# EasyEDA-Schematic.net
KiCad netlist of a schematic drawn in EasyEDA
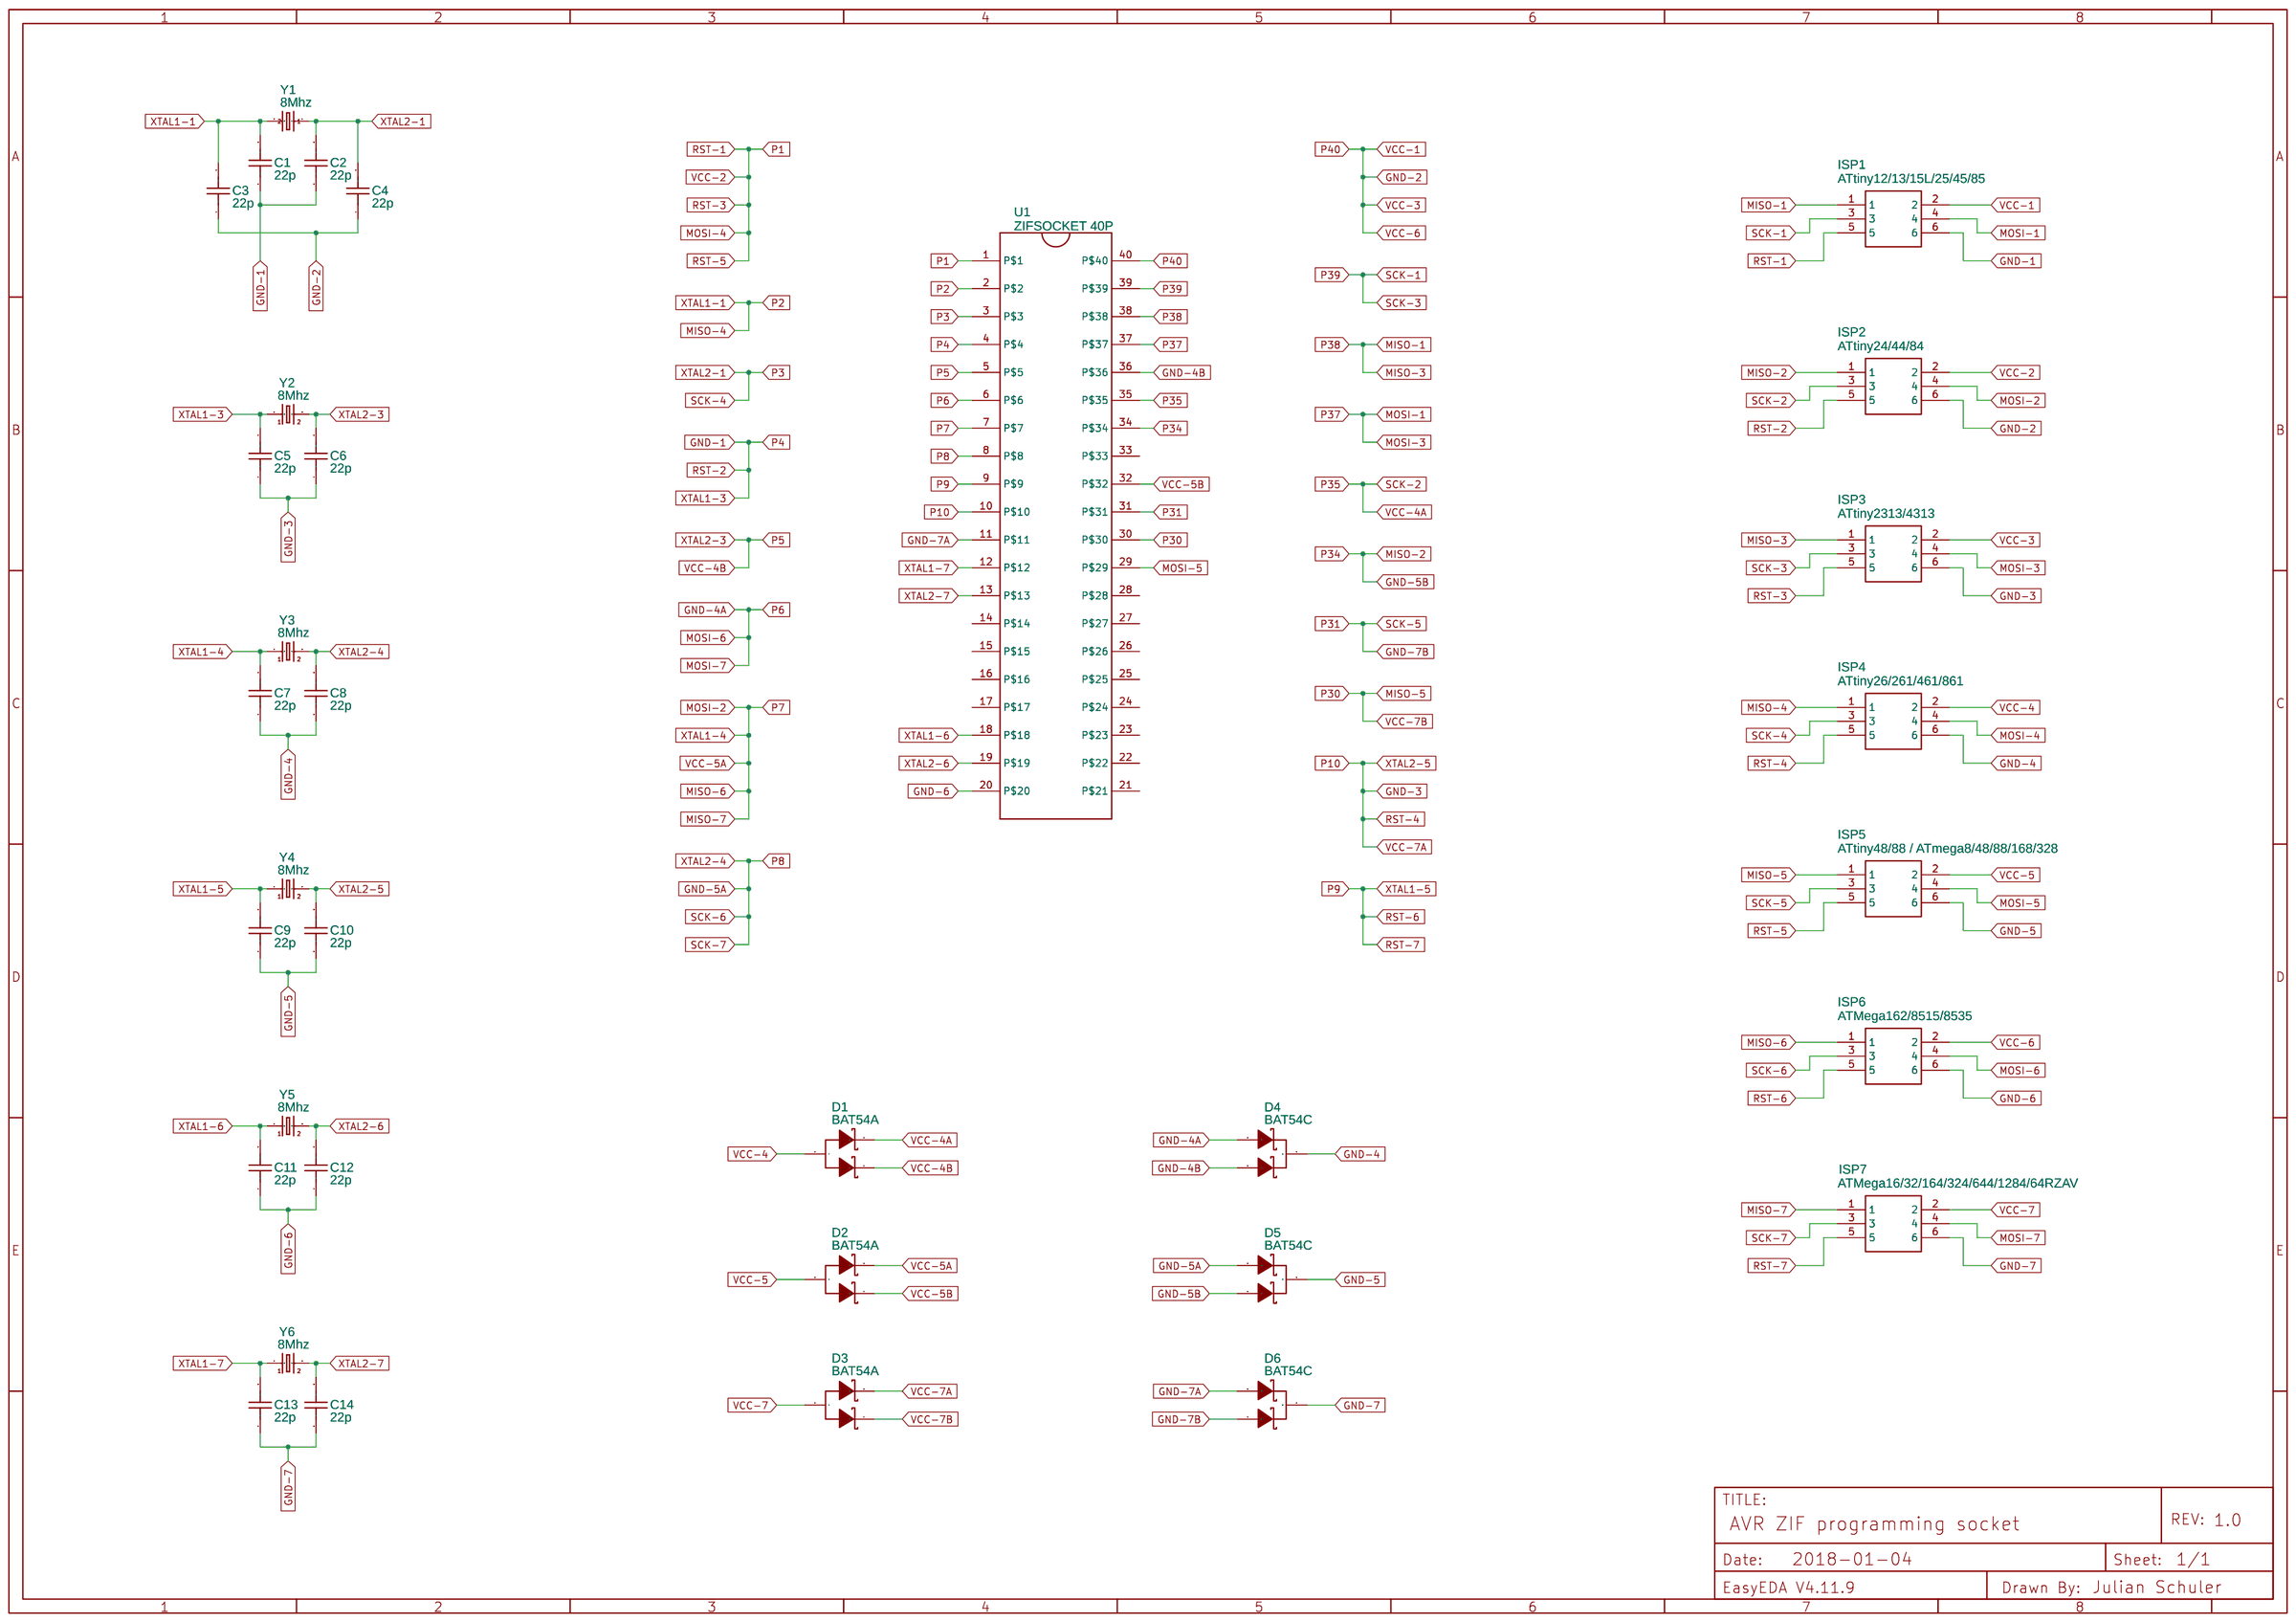
[diagram p0: schematic sheet]

(export (version "E")
  (design (tool "Eeschema 10.0.6"))
  (components
    (comp (ref "C1")
      (value "22p")
      (fields (field (name "BOM_Manufacturer Part") "?"))
      (libsource (lib "") (part "Cap_RAD-0.1_US"))
    )
    (comp (ref "C2")
      (value "22p")
      (fields (field (name "BOM_Manufacturer Part") "?"))
      (libsource (lib "") (part "Cap_RAD-0.1_US"))
    )
    (comp (ref "C3")
      (value "22p")
      (fields (field (name "BOM_Manufacturer Part") "?"))
      (libsource (lib "") (part "Cap_RAD-0.1_US"))
    )
    (comp (ref "C4")
      (value "22p")
      (fields (field (name "BOM_Manufacturer Part") "?"))
      (libsource (lib "") (part "Cap_RAD-0.1_US"))
    )
    (comp (ref "C5")
      (value "22p")
      (fields (field (name "BOM_Manufacturer Part") "?"))
      (libsource (lib "") (part "Cap_RAD-0.1_US"))
    )
    (comp (ref "C6")
      (value "22p")
      (fields (field (name "BOM_Manufacturer Part") "?"))
      (libsource (lib "") (part "Cap_RAD-0.1_US"))
    )
    (comp (ref "C7")
      (value "22p")
      (fields (field (name "BOM_Manufacturer Part") "?"))
      (libsource (lib "") (part "Cap_RAD-0.1_US"))
    )
    (comp (ref "C8")
      (value "22p")
      (fields (field (name "BOM_Manufacturer Part") "?"))
      (libsource (lib "") (part "Cap_RAD-0.1_US"))
    )
    (comp (ref "C9")
      (value "22p")
      (fields (field (name "BOM_Manufacturer Part") "?"))
      (libsource (lib "") (part "Cap_RAD-0.1_US"))
    )
    (comp (ref "C10")
      (value "22p")
      (fields (field (name "BOM_Manufacturer Part") "?"))
      (libsource (lib "") (part "Cap_RAD-0.1_US"))
    )
    (comp (ref "C11")
      (value "22p")
      (fields (field (name "BOM_Manufacturer Part") "?"))
      (libsource (lib "") (part "Cap_RAD-0.1_US"))
    )
    (comp (ref "C12")
      (value "22p")
      (fields (field (name "BOM_Manufacturer Part") "?"))
      (libsource (lib "") (part "Cap_RAD-0.1_US"))
    )
    (comp (ref "C13")
      (value "22p")
      (fields (field (name "BOM_Manufacturer Part") "?"))
      (libsource (lib "") (part "Cap_RAD-0.1_US"))
    )
    (comp (ref "C14")
      (value "22p")
      (fields (field (name "BOM_Manufacturer Part") "?"))
      (libsource (lib "") (part "Cap_RAD-0.1_US"))
    )
    (comp (ref "D1")
      (value "BAT54A")
      (fields (field (name "BOM_Supplier Part") "C83936"))
      (libsource (lib "") (part "Unknown_590_820"))
    )
    (comp (ref "D2")
      (value "BAT54A")
      (fields (field (name "BOM_Supplier Part") "C83936"))
      (libsource (lib "") (part "Unknown_590_910"))
    )
    (comp (ref "D3")
      (value "BAT54A")
      (fields (field (name "BOM_Supplier Part") "C83936"))
      (libsource (lib "") (part "Unknown_590_1000"))
    )
    (comp (ref "D4")
      (value "BAT54C")
      (fields
        (field (name "BOM_Manufacturer Part") "BAT54C(L43)")
        (field (name "BOM_Supplier Part") "C118748")
      )
      (libsource (lib "") (part "Unknown_900_820"))
    )
    (comp (ref "D5")
      (value "BAT54C")
      (fields
        (field (name "BOM_Manufacturer Part") "BAT54C(L43)")
        (field (name "BOM_Supplier Part") "C118748")
      )
      (libsource (lib "") (part "Unknown_900_910"))
    )
    (comp (ref "D6")
      (value "BAT54C")
      (fields
        (field (name "BOM_Manufacturer Part") "BAT54C(L43)")
        (field (name "BOM_Supplier Part") "C118748")
      )
      (libsource (lib "") (part "Unknown_900_1000"))
    )
    (comp (ref "ISP1")
      (value "ATtiny12/13/15L/25/45/85")
      (fields
        (field (name "BOM_Manufacturer Part") "2X3 2.54mm IDC Box")
        (field (name "BOM_Supplier Part") "C11214")
      )
      (libsource (lib "") (part "Unknown_1350_170"))
    )
    (comp (ref "ISP2")
      (value "ATtiny24/44/84")
      (fields
        (field (name "BOM_Manufacturer Part") "2X3 2.54mm IDC Box")
        (field (name "BOM_Supplier Part") "C11214")
      )
      (libsource (lib "") (part "Unknown_1350_290"))
    )
    (comp (ref "ISP3")
      (value "ATtiny2313/4313")
      (fields
        (field (name "BOM_Manufacturer Part") "2X3 2.54mm IDC Box")
        (field (name "BOM_Supplier Part") "C11214")
      )
      (libsource (lib "") (part "Unknown_1350_410"))
    )
    (comp (ref "ISP4")
      (value "ATtiny26/261/461/861")
      (fields
        (field (name "BOM_Manufacturer Part") "2X3 2.54mm IDC Box")
        (field (name "BOM_Supplier Part") "C11214")
      )
      (libsource (lib "") (part "Unknown_1350_530"))
    )
    (comp (ref "ISP5")
      (value "ATtiny48/88 / ATmega8/48/88/168/328")
      (fields
        (field (name "BOM_Manufacturer Part") "2X3 2.54mm IDC Box")
        (field (name "BOM_Supplier Part") "C11214")
      )
      (libsource (lib "") (part "Unknown_1350_650"))
    )
    (comp (ref "ISP6")
      (value "ATMega162/8515/8535")
      (fields
        (field (name "BOM_Manufacturer Part") "2X3 2.54mm IDC Box")
        (field (name "BOM_Supplier Part") "C11214")
      )
      (libsource (lib "") (part "Unknown_1350_770"))
    )
    (comp (ref "ISP7")
      (value "ATMega16/32/164/324/644/1284/64RZAV")
      (fields
        (field (name "BOM_Manufacturer Part") "2X3 2.54mm IDC Box")
        (field (name "BOM_Supplier Part") "C11214")
      )
      (libsource (lib "") (part "Unknown_1350_890"))
    )
    (comp (ref "U1")
      (value "ZIFSOCKET 40P")
      (fields (field (name "BOM_Manufacturer Part") "?"))
      (libsource (lib "") (part "Unknown_750_380"))
    )
    (comp (ref "Y1")
      (value "8Mhz")
      (fields (field (name "BOM_Manufacturer Part") "49S/18PF"))
      (libsource (lib "") (part "Unknown_200_80"))
    )
    (comp (ref "Y2")
      (value "8Mhz")
      (fields (field (name "BOM_Manufacturer Part") "49S/18PF"))
      (libsource (lib "") (part "Unknown_200_290"))
    )
    (comp (ref "Y3")
      (value "8Mhz")
      (fields (field (name "BOM_Manufacturer Part") "49S/18PF"))
      (libsource (lib "") (part "Unknown_200_460"))
    )
    (comp (ref "Y4")
      (value "8Mhz")
      (fields (field (name "BOM_Manufacturer Part") "49S/18PF"))
      (libsource (lib "") (part "Unknown_200_630"))
    )
    (comp (ref "Y5")
      (value "8Mhz")
      (fields (field (name "BOM_Manufacturer Part") "49S/18PF"))
      (libsource (lib "") (part "Unknown_200_800"))
    )
    (comp (ref "Y6")
      (value "8Mhz")
      (fields (field (name "BOM_Manufacturer Part") "49S/18PF"))
      (libsource (lib "") (part "Unknown_200_970"))
    )
  )
  (nets
    (net (code "1") (name "GND-1") (class "Default")
      (node (ref "C1") (pin "1") (pinfunction "1_1") (pintype "unspecified"))
      (node (ref "C2") (pin "1") (pinfunction "1_1") (pintype "unspecified"))
      (node (ref "C5") (pin "2") (pinfunction "2_2") (pintype "unspecified"))
      (node (ref "ISP1") (pin "6") (pinfunction "6_6") (pintype "unspecified"))
      (node (ref "ISP2") (pin "5") (pinfunction "5_5") (pintype "unspecified"))
      (node (ref "U1") (pin "4") (pinfunction "P$4_4") (pintype "unspecified"))
      (node (ref "Y2") (pin "1") (pinfunction "1_1") (pintype "unspecified"))
    )
    (net (code "2") (name "GND-2") (class "Default")
      (node (ref "C3") (pin "1") (pinfunction "1_1") (pintype "unspecified"))
      (node (ref "C4") (pin "1") (pinfunction "1_1") (pintype "unspecified"))
      (node (ref "ISP1") (pin "2") (pinfunction "2_2") (pintype "unspecified"))
      (node (ref "ISP2") (pin "6") (pinfunction "6_6") (pintype "unspecified"))
      (node (ref "ISP3") (pin "2") (pinfunction "2_2") (pintype "unspecified"))
      (node (ref "ISP6") (pin "2") (pinfunction "2_2") (pintype "unspecified"))
      (node (ref "U1") (pin "40") (pinfunction "P$40_40") (pintype "unspecified"))
    )
    (net (code "3") (name "GND-3") (class "Default")
      (node (ref "C10") (pin "2") (pinfunction "2_2") (pintype "unspecified"))
      (node (ref "C5") (pin "1") (pinfunction "1_1") (pintype "unspecified"))
      (node (ref "C6") (pin "1") (pinfunction "1_1") (pintype "unspecified"))
      (node (ref "D3") (pin "2") (pinfunction "K2_2") (pintype "unspecified"))
      (node (ref "ISP3") (pin "6") (pinfunction "6_6") (pintype "unspecified"))
      (node (ref "ISP4") (pin "5") (pinfunction "5_5") (pintype "unspecified"))
      (node (ref "U1") (pin "10") (pinfunction "P$10_10") (pintype "unspecified"))
      (node (ref "Y4") (pin "2") (pinfunction "2_2") (pintype "unspecified"))
    )
    (net (code "4") (name "GND-4") (class "Default")
      (node (ref "C7") (pin "1") (pinfunction "1_1") (pintype "unspecified"))
      (node (ref "C8") (pin "1") (pinfunction "1_1") (pintype "unspecified"))
      (node (ref "D4") (pin "3") (pinfunction "3_3") (pintype "unspecified"))
      (node (ref "ISP4") (pin "6") (pinfunction "6_6") (pintype "unspecified"))
    )
    (net (code "5") (name "GND-4A") (class "Default")
      (node (ref "D4") (pin "2") (pinfunction "2_2") (pintype "unspecified"))
      (node (ref "ISP6") (pin "4") (pinfunction "4_4") (pintype "unspecified"))
      (node (ref "ISP7") (pin "4") (pinfunction "4_4") (pintype "unspecified"))
      (node (ref "U1") (pin "6") (pinfunction "P$6_6") (pintype "unspecified"))
    )
    (net (code "6") (name "GND-4B") (class "Default")
      (node (ref "D4") (pin "1") (pinfunction "1_1") (pintype "unspecified"))
      (node (ref "U1") (pin "36") (pinfunction "P$36_36") (pintype "unspecified"))
    )
    (net (code "7") (name "GND-5") (class "Default")
      (node (ref "C10") (pin "1") (pinfunction "1_1") (pintype "unspecified"))
      (node (ref "C9") (pin "1") (pinfunction "1_1") (pintype "unspecified"))
      (node (ref "D5") (pin "3") (pinfunction "3_3") (pintype "unspecified"))
      (node (ref "ISP5") (pin "6") (pinfunction "6_6") (pintype "unspecified"))
    )
    (net (code "8") (name "GND-5A") (class "Default")
      (node (ref "C8") (pin "2") (pinfunction "2_2") (pintype "unspecified"))
      (node (ref "D5") (pin "2") (pinfunction "2_2") (pintype "unspecified"))
      (node (ref "ISP6") (pin "3") (pinfunction "3_3") (pintype "unspecified"))
      (node (ref "ISP7") (pin "3") (pinfunction "3_3") (pintype "unspecified"))
      (node (ref "U1") (pin "8") (pinfunction "P$8_8") (pintype "unspecified"))
      (node (ref "Y3") (pin "2") (pinfunction "2_2") (pintype "unspecified"))
    )
    (net (code "9") (name "GND-5B") (class "Default")
      (node (ref "D5") (pin "1") (pinfunction "1_1") (pintype "unspecified"))
      (node (ref "ISP2") (pin "1") (pinfunction "1_1") (pintype "unspecified"))
      (node (ref "U1") (pin "34") (pinfunction "P$34_34") (pintype "unspecified"))
    )
    (net (code "10") (name "GND-6") (class "Default")
      (node (ref "C11") (pin "1") (pinfunction "1_1") (pintype "unspecified"))
      (node (ref "C12") (pin "1") (pinfunction "1_1") (pintype "unspecified"))
      (node (ref "ISP6") (pin "6") (pinfunction "6_6") (pintype "unspecified"))
      (node (ref "U1") (pin "20") (pinfunction "P$20_20") (pintype "unspecified"))
    )
    (net (code "11") (name "GND-7") (class "Default")
      (node (ref "C13") (pin "1") (pinfunction "1_1") (pintype "unspecified"))
      (node (ref "C14") (pin "1") (pinfunction "1_1") (pintype "unspecified"))
      (node (ref "D6") (pin "3") (pinfunction "3_3") (pintype "unspecified"))
      (node (ref "ISP7") (pin "6") (pinfunction "6_6") (pintype "unspecified"))
    )
    (net (code "12") (name "GND-7A") (class "Default")
      (node (ref "D6") (pin "2") (pinfunction "2_2") (pintype "unspecified"))
      (node (ref "U1") (pin "11") (pinfunction "P$11_11") (pintype "unspecified"))
    )
    (net (code "13") (name "GND-7B") (class "Default")
      (node (ref "D6") (pin "1") (pinfunction "1_1") (pintype "unspecified"))
      (node (ref "ISP5") (pin "3") (pinfunction "3_3") (pintype "unspecified"))
      (node (ref "U1") (pin "31") (pinfunction "P$31_31") (pintype "unspecified"))
    )
    (net (code "14") (name "MISO-1") (class "Default")
      (node (ref "ISP1") (pin "1") (pinfunction "1_1") (pintype "unspecified"))
      (node (ref "ISP3") (pin "1") (pinfunction "1_1") (pintype "unspecified"))
      (node (ref "U1") (pin "38") (pinfunction "P$38_38") (pintype "unspecified"))
    )
    (net (code "15") (name "MISO-4") (class "Default")
      (node (ref "C1") (pin "2") (pinfunction "2_2") (pintype "unspecified"))
      (node (ref "C3") (pin "2") (pinfunction "2_2") (pintype "unspecified"))
      (node (ref "ISP4") (pin "1") (pinfunction "1_1") (pintype "unspecified"))
      (node (ref "U1") (pin "2") (pinfunction "P$2_2") (pintype "unspecified"))
      (node (ref "Y1") (pin "2") (pinfunction "2_2") (pintype "unspecified"))
    )
    (net (code "16") (name "MISO-5") (class "Default")
      (node (ref "D3") (pin "1") (pinfunction "K1_1") (pintype "unspecified"))
      (node (ref "ISP5") (pin "1") (pinfunction "1_1") (pintype "unspecified"))
      (node (ref "U1") (pin "30") (pinfunction "P$30_30") (pintype "unspecified"))
    )
    (net (code "17") (name "MISO-6") (class "Default")
      (node (ref "C7") (pin "2") (pinfunction "2_2") (pintype "unspecified"))
      (node (ref "D2") (pin "2") (pinfunction "K2_2") (pintype "unspecified"))
      (node (ref "ISP2") (pin "4") (pinfunction "4_4") (pintype "unspecified"))
      (node (ref "ISP6") (pin "1") (pinfunction "1_1") (pintype "unspecified"))
      (node (ref "ISP7") (pin "1") (pinfunction "1_1") (pintype "unspecified"))
      (node (ref "U1") (pin "7") (pinfunction "P$7_7") (pintype "unspecified"))
      (node (ref "Y3") (pin "1") (pinfunction "1_1") (pintype "unspecified"))
    )
    (net (code "18") (name "MOSI-1") (class "Default")
      (node (ref "ISP1") (pin "4") (pinfunction "4_4") (pintype "unspecified"))
      (node (ref "ISP3") (pin "4") (pinfunction "4_4") (pintype "unspecified"))
      (node (ref "U1") (pin "37") (pinfunction "P$37_37") (pintype "unspecified"))
    )
    (net (code "19") (name "MOSI-4") (class "Default")
      (node (ref "ISP1") (pin "5") (pinfunction "5_5") (pintype "unspecified"))
      (node (ref "ISP2") (pin "2") (pinfunction "2_2") (pintype "unspecified"))
      (node (ref "ISP3") (pin "5") (pinfunction "5_5") (pintype "unspecified"))
      (node (ref "ISP4") (pin "4") (pinfunction "4_4") (pintype "unspecified"))
      (node (ref "ISP5") (pin "5") (pinfunction "5_5") (pintype "unspecified"))
      (node (ref "U1") (pin "1") (pinfunction "P$1_1") (pintype "unspecified"))
    )
    (net (code "20") (name "MOSI-5") (class "Default")
      (node (ref "ISP5") (pin "4") (pinfunction "4_4") (pintype "unspecified"))
      (node (ref "U1") (pin "29") (pinfunction "P$29_29") (pintype "unspecified"))
    )
    (net (code "21") (name "P3") (class "Default")
      (node (ref "C2") (pin "2") (pinfunction "2_2") (pintype "unspecified"))
      (node (ref "C4") (pin "2") (pinfunction "2_2") (pintype "unspecified"))
      (node (ref "ISP4") (pin "3") (pinfunction "3_3") (pintype "unspecified"))
      (node (ref "U1") (pin "3") (pinfunction "P$3_3") (pintype "unspecified"))
      (node (ref "Y1") (pin "1") (pinfunction "1_1") (pintype "unspecified"))
    )
    (net (code "22") (name "P5") (class "Default")
      (node (ref "C6") (pin "2") (pinfunction "2_2") (pintype "unspecified"))
      (node (ref "D1") (pin "1") (pinfunction "K1_1") (pintype "unspecified"))
      (node (ref "U1") (pin "5") (pinfunction "P$5_5") (pintype "unspecified"))
      (node (ref "Y2") (pin "2") (pinfunction "2_2") (pintype "unspecified"))
    )
    (net (code "23") (name "P9") (class "Default")
      (node (ref "C9") (pin "2") (pinfunction "2_2") (pintype "unspecified"))
      (node (ref "ISP6") (pin "5") (pinfunction "5_5") (pintype "unspecified"))
      (node (ref "ISP7") (pin "5") (pinfunction "5_5") (pintype "unspecified"))
      (node (ref "U1") (pin "9") (pinfunction "P$9_9") (pintype "unspecified"))
      (node (ref "Y4") (pin "1") (pinfunction "1_1") (pintype "unspecified"))
    )
    (net (code "24") (name "P35") (class "Default")
      (node (ref "D1") (pin "2") (pinfunction "K2_2") (pintype "unspecified"))
      (node (ref "ISP2") (pin "3") (pinfunction "3_3") (pintype "unspecified"))
      (node (ref "U1") (pin "35") (pinfunction "P$35_35") (pintype "unspecified"))
    )
    (net (code "25") (name "P39") (class "Default")
      (node (ref "ISP1") (pin "3") (pinfunction "3_3") (pintype "unspecified"))
      (node (ref "ISP3") (pin "3") (pinfunction "3_3") (pintype "unspecified"))
      (node (ref "U1") (pin "39") (pinfunction "P$39_39") (pintype "unspecified"))
    )
    (net (code "26") (name "VCC-4") (class "Default")
      (node (ref "D1") (pin "3") (pinfunction "A_3") (pintype "unspecified"))
      (node (ref "ISP4") (pin "2") (pinfunction "2_2") (pintype "unspecified"))
    )
    (net (code "27") (name "VCC-5") (class "Default")
      (node (ref "D2") (pin "3") (pinfunction "A_3") (pintype "unspecified"))
      (node (ref "ISP5") (pin "2") (pinfunction "2_2") (pintype "unspecified"))
    )
    (net (code "28") (name "VCC-5B") (class "Default")
      (node (ref "D2") (pin "1") (pinfunction "K1_1") (pintype "unspecified"))
      (node (ref "U1") (pin "32") (pinfunction "P$32_32") (pintype "unspecified"))
    )
    (net (code "29") (name "VCC-7") (class "Default")
      (node (ref "D3") (pin "3") (pinfunction "A_3") (pintype "unspecified"))
      (node (ref "ISP7") (pin "2") (pinfunction "2_2") (pintype "unspecified"))
    )
    (net (code "30") (name "XTAL1-6") (class "Default")
      (node (ref "C11") (pin "2") (pinfunction "2_2") (pintype "unspecified"))
      (node (ref "U1") (pin "18") (pinfunction "P$18_18") (pintype "unspecified"))
      (node (ref "Y5") (pin "1") (pinfunction "1_1") (pintype "unspecified"))
    )
    (net (code "31") (name "XTAL1-7") (class "Default")
      (node (ref "C13") (pin "2") (pinfunction "2_2") (pintype "unspecified"))
      (node (ref "U1") (pin "12") (pinfunction "P$12_12") (pintype "unspecified"))
      (node (ref "Y6") (pin "1") (pinfunction "1_1") (pintype "unspecified"))
    )
    (net (code "32") (name "XTAL2-6") (class "Default")
      (node (ref "C12") (pin "2") (pinfunction "2_2") (pintype "unspecified"))
      (node (ref "U1") (pin "19") (pinfunction "P$19_19") (pintype "unspecified"))
      (node (ref "Y5") (pin "2") (pinfunction "2_2") (pintype "unspecified"))
    )
    (net (code "33") (name "XTAL2-7") (class "Default")
      (node (ref "C14") (pin "2") (pinfunction "2_2") (pintype "unspecified"))
      (node (ref "U1") (pin "13") (pinfunction "P$13_13") (pintype "unspecified"))
      (node (ref "Y6") (pin "2") (pinfunction "2_2") (pintype "unspecified"))
    )
    (net (code "34") (name "unconnected-(U1-P$14-Pad14)") (class "Default")
      (node (ref "U1") (pin "14") (pinfunction "P$14_14") (pintype "unspecified"))
    )
    (net (code "35") (name "unconnected-(U1-P$15-Pad15)") (class "Default")
      (node (ref "U1") (pin "15") (pinfunction "P$15_15") (pintype "unspecified"))
    )
    (net (code "36") (name "unconnected-(U1-P$16-Pad16)") (class "Default")
      (node (ref "U1") (pin "16") (pinfunction "P$16_16") (pintype "unspecified"))
    )
    (net (code "37") (name "unconnected-(U1-P$17-Pad17)") (class "Default")
      (node (ref "U1") (pin "17") (pinfunction "P$17_17") (pintype "unspecified"))
    )
    (net (code "38") (name "unconnected-(U1-P$21-Pad21)") (class "Default")
      (node (ref "U1") (pin "21") (pinfunction "P$21_21") (pintype "unspecified"))
    )
    (net (code "39") (name "unconnected-(U1-P$22-Pad22)") (class "Default")
      (node (ref "U1") (pin "22") (pinfunction "P$22_22") (pintype "unspecified"))
    )
    (net (code "40") (name "unconnected-(U1-P$23-Pad23)") (class "Default")
      (node (ref "U1") (pin "23") (pinfunction "P$23_23") (pintype "unspecified"))
    )
    (net (code "41") (name "unconnected-(U1-P$24-Pad24)") (class "Default")
      (node (ref "U1") (pin "24") (pinfunction "P$24_24") (pintype "unspecified"))
    )
    (net (code "42") (name "unconnected-(U1-P$25-Pad25)") (class "Default")
      (node (ref "U1") (pin "25") (pinfunction "P$25_25") (pintype "unspecified"))
    )
    (net (code "43") (name "unconnected-(U1-P$26-Pad26)") (class "Default")
      (node (ref "U1") (pin "26") (pinfunction "P$26_26") (pintype "unspecified"))
    )
    (net (code "44") (name "unconnected-(U1-P$27-Pad27)") (class "Default")
      (node (ref "U1") (pin "27") (pinfunction "P$27_27") (pintype "unspecified"))
    )
    (net (code "45") (name "unconnected-(U1-P$28-Pad28)") (class "Default")
      (node (ref "U1") (pin "28") (pinfunction "P$28_28") (pintype "unspecified"))
    )
    (net (code "46") (name "unconnected-(U1-P$33-Pad33)") (class "Default")
      (node (ref "U1") (pin "33") (pinfunction "P$33_33") (pintype "unspecified"))
    )
  )
)
